# sc_detector.net
KiCad netlist of a schematic drawn in EAGLE
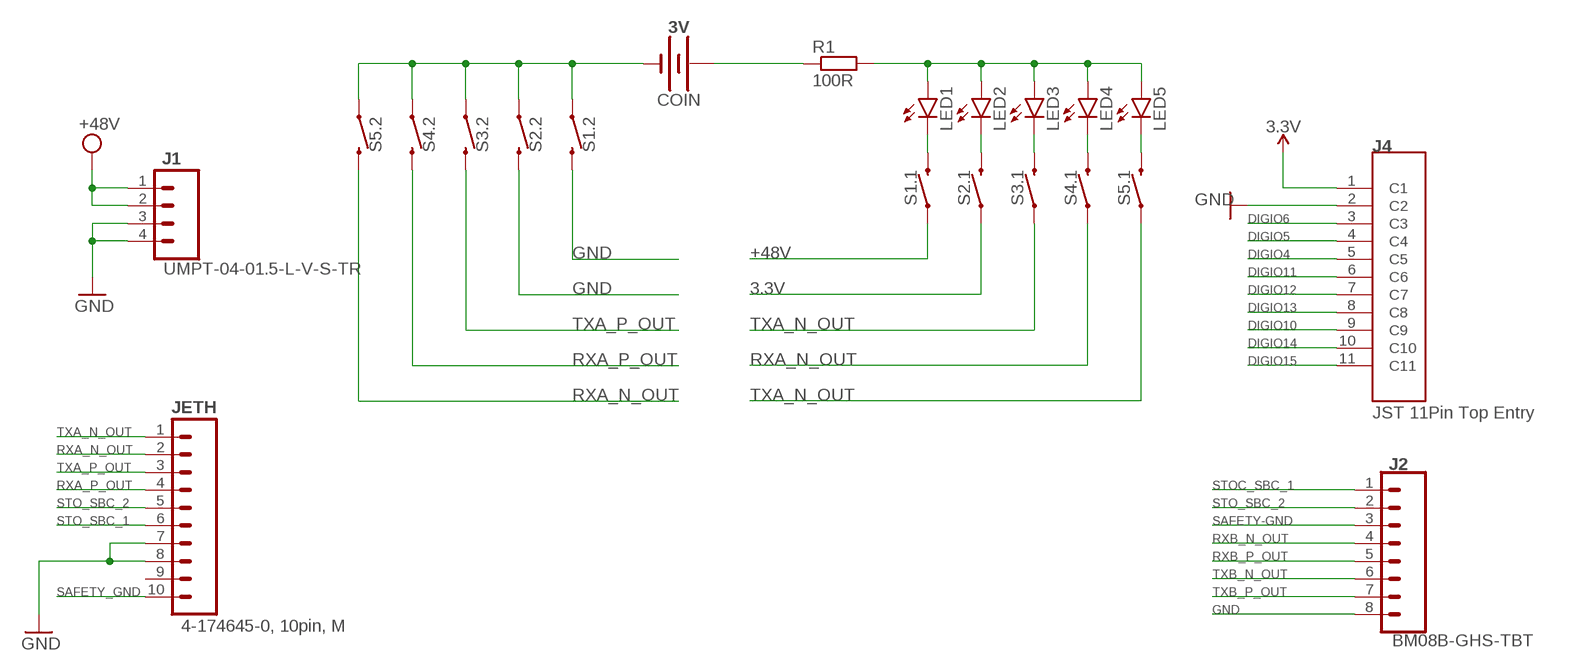
[diagram p0: schematic, sheet 1]

(export (version "E")
  (design (tool "Eeschema 10.0.6"))
  (components
    (comp (ref "COIN")
      (value "3V")
      (footprint "eagle-import:BATTCON_12MM")
      (libsource (lib "eagle-import") (part "BATTERY-12MM_SMD"))
    )
    (comp (ref "J1")
      (value "UMPT-04-01.5-L-V-S-TR")
      (footprint "eagle-import:JST-4-SMD")
      (libsource (lib "eagle-import") (part "CONN_04JST-SMD"))
    )
    (comp (ref "J2")
      (value "BM08B-GHS-TBT")
      (footprint "eagle-import:1X08_SMD_MALE")
      (libsource (lib "eagle-import") (part "CONN_08SMD-MALE"))
    )
    (comp (ref "J4")
      (value "JST 11Pin Top Entry")
      (footprint "eagle-import:ROBCO_CONN")
      (libsource (lib "eagle-import") (part "ROBCO_CONN"))
    )
    (comp (ref "JETH")
      (value "4-174645-0, 10pin, M")
      (footprint "eagle-import:1X10_SMD_MALE")
      (libsource (lib "eagle-import") (part "CONN_10SMD_MALE"))
    )
    (comp (ref "LED1")
      (value "LEDCHIP-LED0805")
      (footprint "eagle-import:CHIP-LED0805")
      (libsource (lib "eagle-import") (part "LEDCHIP-LED0805"))
    )
    (comp (ref "LED2")
      (value "LEDCHIP-LED0805")
      (footprint "eagle-import:CHIP-LED0805")
      (libsource (lib "eagle-import") (part "LEDCHIP-LED0805"))
    )
    (comp (ref "LED3")
      (value "LEDCHIP-LED0805")
      (footprint "eagle-import:CHIP-LED0805")
      (libsource (lib "eagle-import") (part "LEDCHIP-LED0805"))
    )
    (comp (ref "LED4")
      (value "LEDCHIP-LED0805")
      (footprint "eagle-import:CHIP-LED0805")
      (libsource (lib "eagle-import") (part "LEDCHIP-LED0805"))
    )
    (comp (ref "LED5")
      (value "LEDCHIP-LED0805")
      (footprint "eagle-import:CHIP-LED0805")
      (libsource (lib "eagle-import") (part "LEDCHIP-LED0805"))
    )
    (comp (ref "R1")
      (value "100R")
      (footprint "eagle-import:R0805")
      (libsource (lib "eagle-import") (part "R-EU_R0805"))
    )
    (comp (ref "S1.1")
      (value "MOMENTARY-SWITCH-SPST-SMD-6.0X3.5MM")
      (footprint "eagle-import:TACTILE_SWITCH_SMD_6.0X3.5MM")
      (libsource (lib "eagle-import") (part "MOMENTARY-SWITCH-SPST-SMD-6.0X3.5MM"))
    )
    (comp (ref "S1.2")
      (value "MOMENTARY-SWITCH-SPST-SMD-6.0X3.5MM")
      (footprint "eagle-import:TACTILE_SWITCH_SMD_6.0X3.5MM")
      (libsource (lib "eagle-import") (part "MOMENTARY-SWITCH-SPST-SMD-6.0X3.5MM"))
    )
    (comp (ref "S2.1")
      (value "MOMENTARY-SWITCH-SPST-SMD-6.0X3.5MM")
      (footprint "eagle-import:TACTILE_SWITCH_SMD_6.0X3.5MM")
      (libsource (lib "eagle-import") (part "MOMENTARY-SWITCH-SPST-SMD-6.0X3.5MM"))
    )
    (comp (ref "S2.2")
      (value "MOMENTARY-SWITCH-SPST-SMD-6.0X3.5MM")
      (footprint "eagle-import:TACTILE_SWITCH_SMD_6.0X3.5MM")
      (libsource (lib "eagle-import") (part "MOMENTARY-SWITCH-SPST-SMD-6.0X3.5MM"))
    )
    (comp (ref "S3.1")
      (value "MOMENTARY-SWITCH-SPST-SMD-6.0X3.5MM")
      (footprint "eagle-import:TACTILE_SWITCH_SMD_6.0X3.5MM")
      (libsource (lib "eagle-import") (part "MOMENTARY-SWITCH-SPST-SMD-6.0X3.5MM"))
    )
    (comp (ref "S3.2")
      (value "MOMENTARY-SWITCH-SPST-SMD-6.0X3.5MM")
      (footprint "eagle-import:TACTILE_SWITCH_SMD_6.0X3.5MM")
      (libsource (lib "eagle-import") (part "MOMENTARY-SWITCH-SPST-SMD-6.0X3.5MM"))
    )
    (comp (ref "S4.1")
      (value "MOMENTARY-SWITCH-SPST-SMD-6.0X3.5MM")
      (footprint "eagle-import:TACTILE_SWITCH_SMD_6.0X3.5MM")
      (libsource (lib "eagle-import") (part "MOMENTARY-SWITCH-SPST-SMD-6.0X3.5MM"))
    )
    (comp (ref "S4.2")
      (value "MOMENTARY-SWITCH-SPST-SMD-6.0X3.5MM")
      (footprint "eagle-import:TACTILE_SWITCH_SMD_6.0X3.5MM")
      (libsource (lib "eagle-import") (part "MOMENTARY-SWITCH-SPST-SMD-6.0X3.5MM"))
    )
    (comp (ref "S5.1")
      (value "MOMENTARY-SWITCH-SPST-SMD-6.0X3.5MM")
      (footprint "eagle-import:TACTILE_SWITCH_SMD_6.0X3.5MM")
      (libsource (lib "eagle-import") (part "MOMENTARY-SWITCH-SPST-SMD-6.0X3.5MM"))
    )
    (comp (ref "S5.2")
      (value "MOMENTARY-SWITCH-SPST-SMD-6.0X3.5MM")
      (footprint "eagle-import:TACTILE_SWITCH_SMD_6.0X3.5MM")
      (libsource (lib "eagle-import") (part "MOMENTARY-SWITCH-SPST-SMD-6.0X3.5MM"))
    )
  )
  (nets
    (net (code "1") (name "+48V") (class "Default")
      (node (ref "J1") (pin "1") (pinfunction "1_1") (pintype "passive"))
      (node (ref "J1") (pin "2") (pinfunction "2_2") (pintype "passive"))
      (node (ref "S1.1") (pin "1") (pinfunction "1_1") (pintype "passive"))
    )
    (net (code "2") (name "/DIGIO4") (class "Default")
      (node (ref "J4") (pin "5") (pinfunction "C5_5") (pintype "bidirectional"))
    )
    (net (code "3") (name "/DIGIO5") (class "Default")
      (node (ref "J4") (pin "4") (pinfunction "C4_4") (pintype "bidirectional"))
    )
    (net (code "4") (name "/DIGIO6") (class "Default")
      (node (ref "J4") (pin "3") (pinfunction "C3_3") (pintype "bidirectional"))
    )
    (net (code "5") (name "/DIGIO10") (class "Default")
      (node (ref "J4") (pin "9") (pinfunction "C9_9") (pintype "bidirectional"))
    )
    (net (code "6") (name "/DIGIO11") (class "Default")
      (node (ref "J4") (pin "6") (pinfunction "C6_6") (pintype "bidirectional"))
    )
    (net (code "7") (name "/DIGIO12") (class "Default")
      (node (ref "J4") (pin "7") (pinfunction "C7_7") (pintype "bidirectional"))
    )
    (net (code "8") (name "/DIGIO13") (class "Default")
      (node (ref "J4") (pin "8") (pinfunction "C8_8") (pintype "bidirectional"))
    )
    (net (code "9") (name "/DIGIO14") (class "Default")
      (node (ref "J4") (pin "10") (pinfunction "C10_10") (pintype "bidirectional"))
    )
    (net (code "10") (name "/DIGIO15") (class "Default")
      (node (ref "J4") (pin "11") (pinfunction "C11_11") (pintype "bidirectional"))
    )
    (net (code "11") (name "/RXA_N_OUT") (class "Default")
      (node (ref "JETH") (pin "2") (pinfunction "2_2") (pintype "passive"))
      (node (ref "S4.1") (pin "1") (pinfunction "1_1") (pintype "passive"))
      (node (ref "S5.2") (pin "2") (pinfunction "2_2") (pintype "passive"))
    )
    (net (code "12") (name "/RXA_P_OUT") (class "Default")
      (node (ref "JETH") (pin "4") (pinfunction "4_4") (pintype "passive"))
      (node (ref "S4.2") (pin "2") (pinfunction "2_2") (pintype "passive"))
    )
    (net (code "13") (name "/RXB_N_OUT") (class "Default")
      (node (ref "J2") (pin "4") (pinfunction "4_4") (pintype "passive"))
    )
    (net (code "14") (name "/RXB_P_OUT") (class "Default")
      (node (ref "J2") (pin "5") (pinfunction "5_5") (pintype "passive"))
    )
    (net (code "15") (name "/SAFETY-GND") (class "Default")
      (node (ref "J2") (pin "3") (pinfunction "3_3") (pintype "passive"))
    )
    (net (code "16") (name "/SAFETY_GND") (class "Default")
      (node (ref "JETH") (pin "10") (pinfunction "10_10") (pintype "passive"))
    )
    (net (code "17") (name "/STOC_SBC_1") (class "Default")
      (node (ref "J2") (pin "1") (pinfunction "1_1") (pintype "passive"))
    )
    (net (code "18") (name "/STO_SBC_1") (class "Default")
      (node (ref "JETH") (pin "6") (pinfunction "6_6") (pintype "passive"))
    )
    (net (code "19") (name "/STO_SBC_2") (class "Default")
      (node (ref "J2") (pin "2") (pinfunction "2_2") (pintype "passive"))
      (node (ref "JETH") (pin "5") (pinfunction "5_5") (pintype "passive"))
    )
    (net (code "20") (name "/TXA_N_OUT") (class "Default")
      (node (ref "JETH") (pin "1") (pinfunction "1_1") (pintype "passive"))
      (node (ref "S3.1") (pin "1") (pinfunction "1_1") (pintype "passive"))
      (node (ref "S5.1") (pin "1") (pinfunction "1_1") (pintype "passive"))
    )
    (net (code "21") (name "/TXA_P_OUT") (class "Default")
      (node (ref "JETH") (pin "3") (pinfunction "3_3") (pintype "passive"))
      (node (ref "S3.2") (pin "2") (pinfunction "2_2") (pintype "passive"))
    )
    (net (code "22") (name "/TXB_N_OUT") (class "Default")
      (node (ref "J2") (pin "6") (pinfunction "6_6") (pintype "passive"))
    )
    (net (code "23") (name "/TXB_P_OUT") (class "Default")
      (node (ref "J2") (pin "7") (pinfunction "7_7") (pintype "passive"))
    )
    (net (code "24") (name "3.3V") (class "Default")
      (node (ref "J4") (pin "1") (pinfunction "C1_1") (pintype "bidirectional"))
      (node (ref "S2.1") (pin "1") (pinfunction "1_1") (pintype "passive"))
    )
    (net (code "25") (name "GND") (class "Default")
      (node (ref "J1") (pin "3") (pinfunction "3_3") (pintype "passive"))
      (node (ref "J1") (pin "4") (pinfunction "4_4") (pintype "passive"))
      (node (ref "J2") (pin "8") (pinfunction "8_8") (pintype "passive"))
      (node (ref "J4") (pin "2") (pinfunction "C2_2") (pintype "bidirectional"))
      (node (ref "JETH") (pin "7") (pinfunction "7_7") (pintype "passive"))
      (node (ref "JETH") (pin "8") (pinfunction "8_8") (pintype "passive"))
      (node (ref "S1.2") (pin "2") (pinfunction "2_2") (pintype "passive"))
      (node (ref "S2.2") (pin "2") (pinfunction "2_2") (pintype "passive"))
    )
    (net (code "26") (name "Net-(COIN-+)") (class "Default")
      (node (ref "COIN") (pin "PWR@1") (pinfunction "+_PWR@1") (pintype "power_in"))
      (node (ref "R1") (pin "1") (pinfunction "1_1") (pintype "passive"))
    )
    (net (code "27") (name "Net-(COIN--)") (class "Default")
      (node (ref "COIN") (pin "GND") (pinfunction "-_GND") (pintype "power_in"))
      (node (ref "S1.2") (pin "1") (pinfunction "1_1") (pintype "passive"))
      (node (ref "S2.2") (pin "1") (pinfunction "1_1") (pintype "passive"))
      (node (ref "S3.2") (pin "1") (pinfunction "1_1") (pintype "passive"))
      (node (ref "S4.2") (pin "1") (pinfunction "1_1") (pintype "passive"))
      (node (ref "S5.2") (pin "1") (pinfunction "1_1") (pintype "passive"))
    )
    (net (code "28") (name "Net-(LED1-PadA)") (class "Default")
      (node (ref "LED1") (pin "A") (pinfunction "A_A") (pintype "passive"))
      (node (ref "LED2") (pin "A") (pinfunction "A_A") (pintype "passive"))
      (node (ref "LED3") (pin "A") (pinfunction "A_A") (pintype "passive"))
      (node (ref "LED4") (pin "A") (pinfunction "A_A") (pintype "passive"))
      (node (ref "LED5") (pin "A") (pinfunction "A_A") (pintype "passive"))
      (node (ref "R1") (pin "2") (pinfunction "2_2") (pintype "passive"))
    )
    (net (code "29") (name "Net-(LED1-PadC)") (class "Default")
      (node (ref "LED1") (pin "C") (pinfunction "C_C") (pintype "passive"))
      (node (ref "S1.1") (pin "2") (pinfunction "2_2") (pintype "passive"))
    )
    (net (code "30") (name "Net-(LED2-PadC)") (class "Default")
      (node (ref "LED2") (pin "C") (pinfunction "C_C") (pintype "passive"))
      (node (ref "S2.1") (pin "2") (pinfunction "2_2") (pintype "passive"))
    )
    (net (code "31") (name "Net-(LED3-PadC)") (class "Default")
      (node (ref "LED3") (pin "C") (pinfunction "C_C") (pintype "passive"))
      (node (ref "S3.1") (pin "2") (pinfunction "2_2") (pintype "passive"))
    )
    (net (code "32") (name "Net-(LED4-PadC)") (class "Default")
      (node (ref "LED4") (pin "C") (pinfunction "C_C") (pintype "passive"))
      (node (ref "S4.1") (pin "2") (pinfunction "2_2") (pintype "passive"))
    )
    (net (code "33") (name "Net-(LED5-PadC)") (class "Default")
      (node (ref "LED5") (pin "C") (pinfunction "C_C") (pintype "passive"))
      (node (ref "S5.1") (pin "2") (pinfunction "2_2") (pintype "passive"))
    )
    (net (code "34") (name "unconnected-(JETH-Pad9)") (class "Default")
      (node (ref "JETH") (pin "9") (pinfunction "9_9") (pintype "passive"))
    )
  )
)
